# Peripheral_Circuit_A.net
KiCad netlist of a schematic drawn in Altium Designer
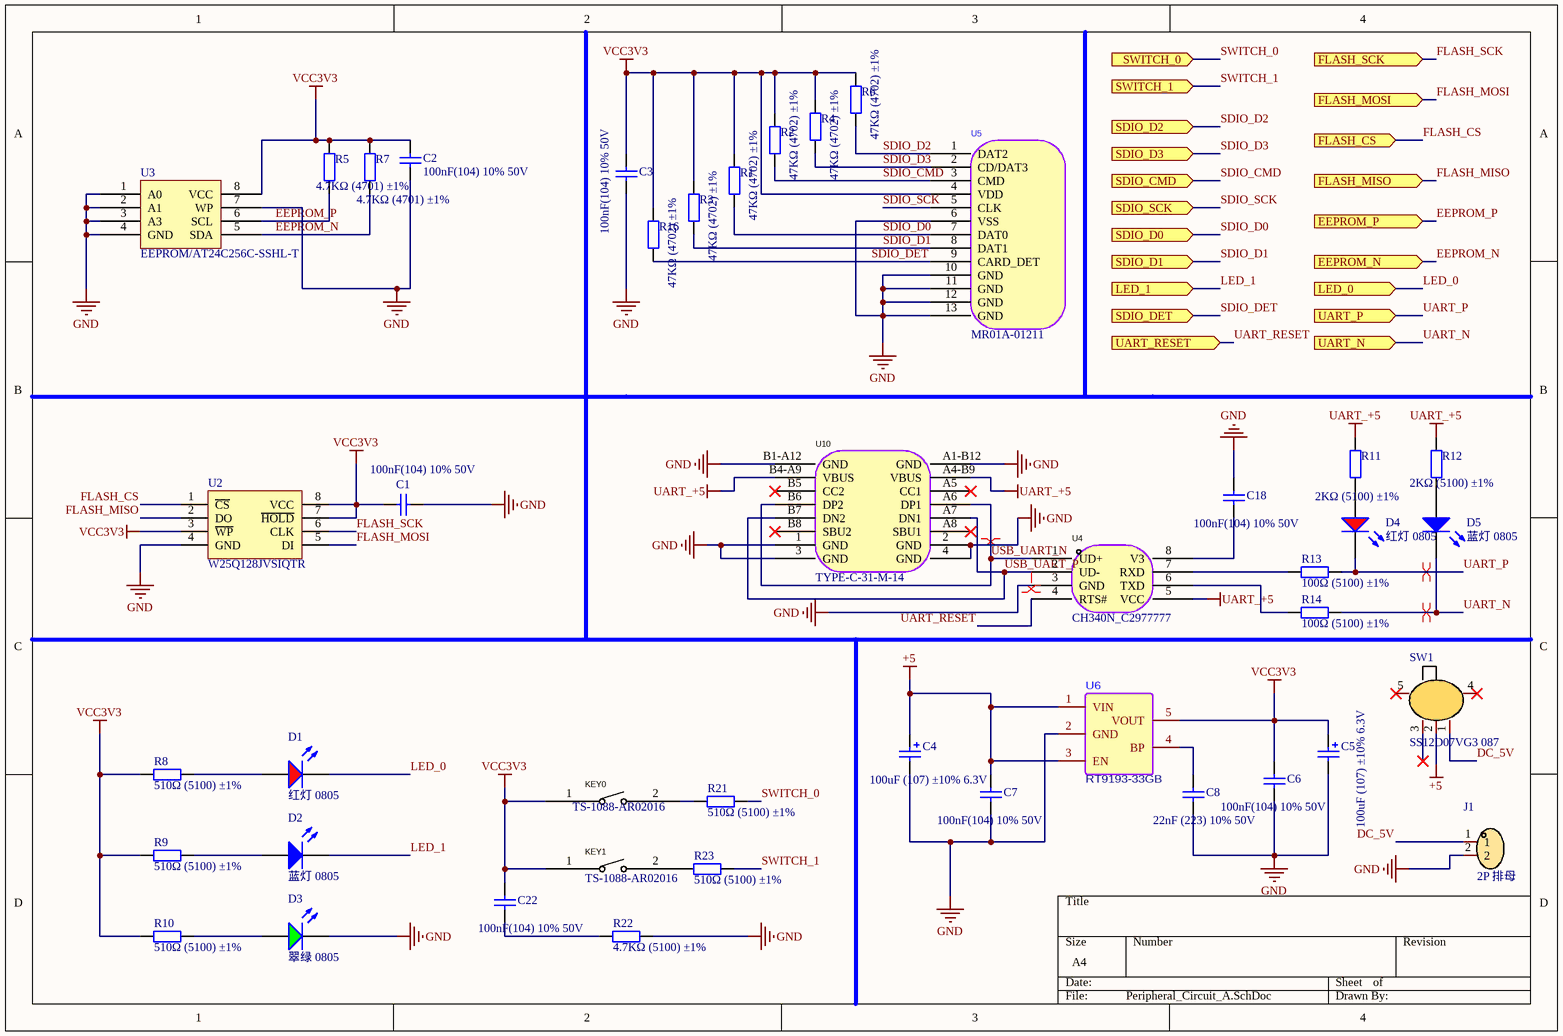
[diagram p0: Peripheral_Circuit_A.SchDoc]

(export (version "E")
  (design (tool "Eeschema 10.0.6"))
  (components
    (comp (ref "C1")
      (value "100nF(104) 10% 50V")
      (footprint "0805_C")
      (description "贴片电容")
      (libsource (lib "Miscellaneous Devices LC") (part "0805 100nF(104) 10% 50V"))
    )
    (comp (ref "C2")
      (value "100nF(104) 10% 50V")
      (footprint "0805_C")
      (description "贴片电容")
      (libsource (lib "Miscellaneous Devices LC") (part "0805 100nF(104) 10% 50V"))
    )
    (comp (ref "C3")
      (value "100nF(104) 10% 50V")
      (footprint "0805_C")
      (description "贴片电容")
      (libsource (lib "Miscellaneous Devices LC") (part "0805 100nF(104) 10% 50V"))
    )
    (comp (ref "C4")
      (value "100uF (107) ±10% 6.3V")
      (footprint "CASE-B_3528")
      (description "钽电容")
      (libsource (lib "Miscellaneous Devices LC") (part "3528 100uF (107) 10% 6.3V"))
    )
    (comp (ref "C5")
      (value "100uF (107) ±10% 6.3V")
      (footprint "CASE-B_3528")
      (description "钽电容")
      (libsource (lib "Miscellaneous Devices LC") (part "3528 100uF (107) 10% 6.3V"))
    )
    (comp (ref "C6")
      (value "100nF(104) 10% 50V")
      (footprint "0805_C")
      (description "贴片电容")
      (libsource (lib "Miscellaneous Devices LC") (part "0805 100nF(104) 10% 50V"))
    )
    (comp (ref "C7")
      (value "100nF(104) 10% 50V")
      (footprint "0805_C")
      (description "贴片电容")
      (libsource (lib "Miscellaneous Devices LC") (part "0805 100nF(104) 10% 50V"))
    )
    (comp (ref "C8")
      (value "22nF (223) 10% 50V")
      (footprint "0805_C")
      (description "贴片电容")
      (libsource (lib "Miscellaneous Devices LC") (part "0805 22nF (223) 10% 50V"))
    )
    (comp (ref "C18")
      (value "100nF(104) 10% 50V")
      (footprint "0805_C")
      (description "贴片电容")
      (libsource (lib "Miscellaneous Devices LC") (part "0805 100nF(104) 10% 50V"))
    )
    (comp (ref "C22")
      (value "100nF(104) 10% 50V")
      (footprint "0805_C")
      (description "贴片电容")
      (libsource (lib "Miscellaneous Devices LC") (part "0805 100nF(104) 10% 50V"))
    )
    (comp (ref "D1")
      (value "红灯 0805")
      (footprint "0805_LED_S1")
      (description "发光二极管")
      (libsource (lib "LED") (part "0805 红灯"))
    )
    (comp (ref "D2")
      (value "蓝灯 0805")
      (footprint "0805_LED_S1")
      (description "发光二极管")
      (libsource (lib "LED") (part "0805 蓝灯"))
    )
    (comp (ref "D3")
      (value "翠绿 0805")
      (footprint "0805_LED_S1")
      (description "发光二极管")
      (libsource (lib "LED") (part "0805 翠绿"))
    )
    (comp (ref "D4")
      (value "红灯 0805")
      (footprint "0805_LED_S1")
      (description "发光二极管")
      (libsource (lib "LED") (part "0805 红灯"))
    )
    (comp (ref "D5")
      (value "蓝灯 0805")
      (footprint "0805_LED_S1")
      (description "发光二极管")
      (libsource (lib "LED") (part "0805 蓝灯"))
    )
    (comp (ref "J1")
      (value "2P 排母")
      (footprint "PM254-1-02-W-8.5")
      (description "2p弯针")
      (fields
        (field (name "MANUFACTURER") "HCTL(华灿天禄)")
        (field (name "MANUFACTURER PART") "PM254-1-02-W-8.5")
      )
      (libsource (lib "EXTRA") (part "PM254-1-02-W-8.5"))
    )
    (comp (ref "KEY0")
      (value "TS-1088-AR02016")
      (footprint "SW-SMD_L3.9-W3.0-P4.45")
      (description "轻触开关")
      (fields (field (name "MANUFACTURER") "XUNPU(讯普)"))
      (libsource (lib "EXTRA") (part "TS-1088-AR02016"))
    )
    (comp (ref "KEY1")
      (value "TS-1088-AR02016")
      (footprint "SW-SMD_L3.9-W3.0-P4.45")
      (description "轻触开关")
      (fields (field (name "MANUFACTURER") "XUNPU(讯普)"))
      (libsource (lib "EXTRA") (part "TS-1088-AR02016"))
    )
    (comp (ref "R1")
      (value "47KΩ (4702) ±1%")
      (footprint "0805_R")
      (description "贴片电阻")
      (libsource (lib "Miscellaneous Devices LC") (part "0805 47KΩ (4702) 1%"))
    )
    (comp (ref "R2")
      (value "47KΩ (4702) ±1%")
      (footprint "0805_R")
      (description "贴片电阻")
      (libsource (lib "Miscellaneous Devices LC") (part "0805 47KΩ (4702) 1%"))
    )
    (comp (ref "R3")
      (value "47KΩ (4702) ±1%")
      (footprint "0805_R")
      (description "贴片电阻")
      (libsource (lib "Miscellaneous Devices LC") (part "0805 47KΩ (4702) 1%"))
    )
    (comp (ref "R4")
      (value "47KΩ (4702) ±1%")
      (footprint "0805_R")
      (description "贴片电阻")
      (libsource (lib "Miscellaneous Devices LC") (part "0805 47KΩ (4702) 1%"))
    )
    (comp (ref "R5")
      (value "4.7KΩ (4701) ±1%")
      (footprint "0805_R")
      (description "贴片电阻")
      (libsource (lib "Miscellaneous Devices LC") (part "0805 4.7KΩ (4701) 1%"))
    )
    (comp (ref "R6")
      (value "47KΩ (4702) ±1%")
      (footprint "0805_R")
      (description "贴片电阻")
      (libsource (lib "Miscellaneous Devices LC") (part "0805 47KΩ (4702) 1%"))
    )
    (comp (ref "R7")
      (value "4.7KΩ (4701) ±1%")
      (footprint "0805_R")
      (description "贴片电阻")
      (libsource (lib "Miscellaneous Devices LC") (part "0805 4.7KΩ (4701) 1%"))
    )
    (comp (ref "R8")
      (value "510Ω (5100) ±1%")
      (footprint "0805_R")
      (description "贴片电阻")
      (libsource (lib "Miscellaneous Devices LC") (part "0805 510Ω (5100) 1%"))
    )
    (comp (ref "R9")
      (value "510Ω (5100) ±1%")
      (footprint "0805_R")
      (description "贴片电阻")
      (libsource (lib "Miscellaneous Devices LC") (part "0805 510Ω (5100) 1%"))
    )
    (comp (ref "R10")
      (value "510Ω (5100) ±1%")
      (footprint "0805_R")
      (description "贴片电阻")
      (libsource (lib "Miscellaneous Devices LC") (part "0805 510Ω (5100) 1%"))
    )
    (comp (ref "R11")
      (value "2KΩ (5100) ±1%")
      (footprint "0805_R")
      (description "贴片电阻")
      (libsource (lib "") (part "0805 510Ω (5100) 1%_1"))
    )
    (comp (ref "R12")
      (value "2KΩ (5100) ±1%")
      (footprint "0805_R")
      (description "贴片电阻")
      (libsource (lib "") (part "0805 510Ω (5100) 1%_1"))
    )
    (comp (ref "R13")
      (value "100Ω (5100) ±1%")
      (footprint "0805_R")
      (description "贴片电阻")
      (libsource (lib "Miscellaneous Devices LC") (part "0805 510Ω (5100) 1%"))
    )
    (comp (ref "R14")
      (value "100Ω (5100) ±1%")
      (footprint "0805_R")
      (description "贴片电阻")
      (libsource (lib "Miscellaneous Devices LC") (part "0805 510Ω (5100) 1%"))
    )
    (comp (ref "R16")
      (value "47KΩ (4702) ±1%")
      (footprint "0805_R")
      (description "贴片电阻")
      (libsource (lib "Miscellaneous Devices LC") (part "0805 47KΩ (4702) 1%"))
    )
    (comp (ref "R21")
      (value "510Ω (5100) ±1%")
      (footprint "0805_R")
      (description "贴片电阻")
      (libsource (lib "Miscellaneous Devices LC") (part "0805 510Ω (5100) 1%"))
    )
    (comp (ref "R22")
      (value "4.7KΩ (5100) ±1%")
      (footprint "0805_R")
      (description "贴片电阻")
      (libsource (lib "") (part "0805 510Ω (5100) 1%_2"))
    )
    (comp (ref "R23")
      (value "510Ω (5100) ±1%")
      (footprint "0805_R")
      (description "贴片电阻")
      (libsource (lib "Miscellaneous Devices LC") (part "0805 510Ω (5100) 1%"))
    )
    (comp (ref "SW1")
      (value "SS12D07VG3 087")
      (footprint "SS12D07VG3")
      (description "直插贴片开关")
      (fields (field (name "MANUFACTURER") "SHOU HAN(首韩)"))
      (libsource (lib "EXTRA") (part "SS12D07VG3 087"))
    )
    (comp (ref "U2")
      (value "W25Q128JVSIQTR")
      (footprint "CH340_N")
      (description "Flash ROM")
      (libsource (lib "IC") (part "W25Q128JVSIQTR_[C97521]"))
    )
    (comp (ref "U3")
      (value "EEPROM/AT24C256C-SSHL-T")
      (footprint "CH340_N")
      (description "EEPROM")
      (libsource (lib "IC") (part "EEPROM/AT24C256C-SSHL-T_[C6482]"))
    )
    (comp (ref "U4")
      (value "CH340N_C2977777")
      (footprint "CH340_N")
      (description "TTL串口phy")
      (fields (field (name "DESIGNER") "U?"))
      (libsource (lib "EXTRA") (part "CH340N_C2977777"))
    )
    (comp (ref "U5")
      (value "MR01A-01211")
      (footprint "TF-SMD_MR01A-01211")
      (fields (field (name "MANUFACTURER") "ATOM(爱特姆)"))
      (libsource (lib "EXTRA") (part "MR01A-01211"))
    )
    (comp (ref "U6")
      (value "RT9193-33GB")
      (footprint "RT9193-33GB")
      (libsource (lib "EXTRA") (part "RT9193-33GB"))
    )
    (comp (ref "U10")
      (value "TYPE-C-31-M-14")
      (footprint "TYPE-C-31-M-14")
      (description "type-c接口")
      (fields (field (name "MANUFACTURER") "韩国韩荣"))
      (libsource (lib "EXTRA") (part "TYPE-C-31-M-14_1"))
    )
  )
  (nets
    (net (code "1") (name "+5") (class "Default")
      (node (ref "C4") (pin "1") (pinfunction "1_1") (pintype "passive"))
      (node (ref "C7") (pin "2") (pinfunction "2_2") (pintype "passive"))
      (node (ref "SW1") (pin "2") (pinfunction "2_2") (pintype "passive"))
      (node (ref "U6") (pin "1") (pinfunction "VIN_1") (pintype "passive"))
      (node (ref "U6") (pin "3") (pinfunction "EN_3") (pintype "passive"))
    )
    (net (code "2") (name "/DC_5V") (class "Default")
      (node (ref "J1") (pin "1") (pinfunction "1_1") (pintype "passive"))
      (node (ref "SW1") (pin "1") (pinfunction "1_1") (pintype "passive"))
    )
    (net (code "3") (name "/EEPROM_N") (class "Default")
      (node (ref "R7") (pin "1") (pinfunction "1_1") (pintype "passive"))
      (node (ref "U3") (pin "5") (pinfunction "SDA_5") (pintype "passive"))
    )
    (net (code "4") (name "/EEPROM_P") (class "Default")
      (node (ref "R5") (pin "1") (pinfunction "1_1") (pintype "passive"))
      (node (ref "U3") (pin "6") (pinfunction "SCL_6") (pintype "passive"))
    )
    (net (code "5") (name "/FLASH_CS") (class "Default")
      (node (ref "U2") (pin "1") (pinfunction "~{CS}_1") (pintype "passive"))
    )
    (net (code "6") (name "/FLASH_MISO") (class "Default")
      (node (ref "U2") (pin "2") (pinfunction "DO_2") (pintype "passive"))
    )
    (net (code "7") (name "/FLASH_MOSI") (class "Default")
      (node (ref "U2") (pin "5") (pinfunction "DI_5") (pintype "passive"))
    )
    (net (code "8") (name "/FLASH_SCK") (class "Default")
      (node (ref "U2") (pin "6") (pinfunction "CLK_6") (pintype "passive"))
    )
    (net (code "9") (name "/LED_0") (class "Default")
      (node (ref "D1") (pin "K") (pinfunction "K_K") (pintype "passive"))
    )
    (net (code "10") (name "/LED_1") (class "Default")
      (node (ref "D2") (pin "K") (pinfunction "K_K") (pintype "passive"))
    )
    (net (code "11") (name "/SDIO_CMD") (class "Default")
      (node (ref "R2") (pin "1") (pinfunction "1_1") (pintype "passive"))
      (node (ref "U5") (pin "3") (pinfunction "CMD_3") (pintype "passive"))
    )
    (net (code "12") (name "/SDIO_D0") (class "Default")
      (node (ref "R1") (pin "1") (pinfunction "1_1") (pintype "passive"))
      (node (ref "U5") (pin "7") (pinfunction "DAT0_7") (pintype "passive"))
    )
    (net (code "13") (name "/SDIO_D1") (class "Default")
      (node (ref "R3") (pin "1") (pinfunction "1_1") (pintype "passive"))
      (node (ref "U5") (pin "8") (pinfunction "DAT1_8") (pintype "passive"))
    )
    (net (code "14") (name "/SDIO_D2") (class "Default")
      (node (ref "R6") (pin "1") (pinfunction "1_1") (pintype "passive"))
      (node (ref "U5") (pin "1") (pinfunction "DAT2_1") (pintype "passive"))
    )
    (net (code "15") (name "/SDIO_D3") (class "Default")
      (node (ref "R4") (pin "1") (pinfunction "1_1") (pintype "passive"))
      (node (ref "U5") (pin "2") (pinfunction "CD/DAT3_2") (pintype "passive"))
    )
    (net (code "16") (name "/SDIO_DET") (class "Default")
      (node (ref "R16") (pin "1") (pinfunction "1_1") (pintype "passive"))
      (node (ref "U5") (pin "9") (pinfunction "CARD_DET_9") (pintype "passive"))
    )
    (net (code "17") (name "/SDIO_SCK") (class "Default")
      (node (ref "U5") (pin "5") (pinfunction "CLK_5") (pintype "passive"))
    )
    (net (code "18") (name "/SWITCH_0") (class "Default")
      (node (ref "R21") (pin "2") (pinfunction "2_2") (pintype "passive"))
    )
    (net (code "19") (name "/SWITCH_1") (class "Default")
      (node (ref "R23") (pin "2") (pinfunction "2_2") (pintype "passive"))
    )
    (net (code "20") (name "/UART_N") (class "Default")
      (node (ref "D5") (pin "K") (pinfunction "K_K") (pintype "passive"))
      (node (ref "R14") (pin "2") (pinfunction "2_2") (pintype "passive"))
    )
    (net (code "21") (name "/UART_P") (class "Default")
      (node (ref "D4") (pin "K") (pinfunction "K_K") (pintype "passive"))
      (node (ref "R13") (pin "2") (pinfunction "2_2") (pintype "passive"))
    )
    (net (code "22") (name "/UART_RESET") (class "Default")
      (node (ref "U4") (pin "4") (pinfunction "RTS#_4") (pintype "passive"))
    )
    (net (code "23") (name "/USB_UART_N") (class "Default")
      (node (ref "U10") (pin "A6") (pinfunction "DP1_A6") (pintype "passive"))
      (node (ref "U10") (pin "B6") (pinfunction "DP2_B6") (pintype "passive"))
      (node (ref "U4") (pin "1") (pinfunction "UD+_1") (pintype "passive"))
    )
    (net (code "24") (name "/USB_UART_P") (class "Default")
      (node (ref "U10") (pin "A7") (pinfunction "DN1_A7") (pintype "passive"))
      (node (ref "U10") (pin "B7") (pinfunction "DN2_B7") (pintype "passive"))
      (node (ref "U4") (pin "2") (pinfunction "UD-_2") (pintype "passive"))
    )
    (net (code "25") (name "GND") (class "Default")
      (node (ref "C1") (pin "2") (pinfunction "2_2") (pintype "passive"))
      (node (ref "C18") (pin "1") (pinfunction "1_1") (pintype "passive"))
      (node (ref "C2") (pin "1") (pinfunction "1_1") (pintype "passive"))
      (node (ref "C3") (pin "1") (pinfunction "1_1") (pintype "passive"))
      (node (ref "C4") (pin "2") (pinfunction "2_2") (pintype "passive"))
      (node (ref "C5") (pin "2") (pinfunction "2_2") (pintype "passive"))
      (node (ref "C6") (pin "1") (pinfunction "1_1") (pintype "passive"))
      (node (ref "C7") (pin "1") (pinfunction "1_1") (pintype "passive"))
      (node (ref "C8") (pin "1") (pinfunction "1_1") (pintype "passive"))
      (node (ref "D3") (pin "K") (pinfunction "K_K") (pintype "passive"))
      (node (ref "J1") (pin "2") (pinfunction "2_2") (pintype "passive"))
      (node (ref "R22") (pin "1") (pinfunction "1_1") (pintype "passive"))
      (node (ref "U10") (pin "1") (pinfunction "GND_1") (pintype "passive"))
      (node (ref "U10") (pin "2") (pinfunction "GND_2") (pintype "passive"))
      (node (ref "U10") (pin "3") (pinfunction "GND_3") (pintype "passive"))
      (node (ref "U10") (pin "4") (pinfunction "GND_4") (pintype "passive"))
      (node (ref "U10") (pin "A1-B12") (pinfunction "GND_A1-B12") (pintype "passive"))
      (node (ref "U10") (pin "B1-A12") (pinfunction "GND_B1-A12") (pintype "passive"))
      (node (ref "U2") (pin "4") (pinfunction "GND_4") (pintype "passive"))
      (node (ref "U3") (pin "1") (pinfunction "A0_1") (pintype "passive"))
      (node (ref "U3") (pin "2") (pinfunction "A1_2") (pintype "passive"))
      (node (ref "U3") (pin "3") (pinfunction "A3_3") (pintype "passive"))
      (node (ref "U3") (pin "4") (pinfunction "GND_4") (pintype "passive"))
      (node (ref "U3") (pin "7") (pinfunction "WP_7") (pintype "passive"))
      (node (ref "U4") (pin "3") (pinfunction "GND_3") (pintype "passive"))
      (node (ref "U5") (pin "10") (pinfunction "GND_10") (pintype "passive"))
      (node (ref "U5") (pin "11") (pinfunction "GND_11") (pintype "passive"))
      (node (ref "U5") (pin "12") (pinfunction "GND_12") (pintype "passive"))
      (node (ref "U5") (pin "13") (pinfunction "GND_13") (pintype "passive"))
      (node (ref "U5") (pin "6") (pinfunction "VSS_6") (pintype "passive"))
      (node (ref "U6") (pin "2") (pinfunction "GND_2") (pintype "passive"))
    )
    (net (code "26") (name "Net-(C22-Pad1)") (class "Default")
      (node (ref "C22") (pin "1") (pinfunction "1_1") (pintype "passive"))
      (node (ref "R22") (pin "2") (pinfunction "2_2") (pintype "passive"))
    )
    (net (code "27") (name "Net-(D1-PadA)") (class "Default")
      (node (ref "D1") (pin "A") (pinfunction "A_A") (pintype "passive"))
      (node (ref "R8") (pin "2") (pinfunction "2_2") (pintype "passive"))
    )
    (net (code "28") (name "Net-(D2-PadA)") (class "Default")
      (node (ref "D2") (pin "A") (pinfunction "A_A") (pintype "passive"))
      (node (ref "R9") (pin "2") (pinfunction "2_2") (pintype "passive"))
    )
    (net (code "29") (name "Net-(D3-PadA)") (class "Default")
      (node (ref "D3") (pin "A") (pinfunction "A_A") (pintype "passive"))
      (node (ref "R10") (pin "2") (pinfunction "2_2") (pintype "passive"))
    )
    (net (code "30") (name "Net-(D4-PadA)") (class "Default")
      (node (ref "D4") (pin "A") (pinfunction "A_A") (pintype "passive"))
      (node (ref "R11") (pin "1") (pinfunction "1_1") (pintype "passive"))
    )
    (net (code "31") (name "Net-(D5-PadA)") (class "Default")
      (node (ref "D5") (pin "A") (pinfunction "A_A") (pintype "passive"))
      (node (ref "R12") (pin "1") (pinfunction "1_1") (pintype "passive"))
    )
    (net (code "32") (name "Net-(KEY0-Pad2)") (class "Default")
      (node (ref "KEY0") (pin "2") (pinfunction "2_2") (pintype "passive"))
      (node (ref "R21") (pin "1") (pinfunction "1_1") (pintype "passive"))
    )
    (net (code "33") (name "Net-(KEY1-Pad2)") (class "Default")
      (node (ref "KEY1") (pin "2") (pinfunction "2_2") (pintype "passive"))
      (node (ref "R23") (pin "1") (pinfunction "1_1") (pintype "passive"))
    )
    (net (code "34") (name "Net-(U4-RXD)") (class "Default")
      (node (ref "R13") (pin "1") (pinfunction "1_1") (pintype "passive"))
      (node (ref "U4") (pin "7") (pinfunction "RXD_7") (pintype "passive"))
    )
    (net (code "35") (name "Net-(U4-TXD)") (class "Default")
      (node (ref "R14") (pin "1") (pinfunction "1_1") (pintype "passive"))
      (node (ref "U4") (pin "6") (pinfunction "TXD_6") (pintype "passive"))
    )
    (net (code "36") (name "Net-(U4-V3)") (class "Default")
      (node (ref "C18") (pin "2") (pinfunction "2_2") (pintype "passive"))
      (node (ref "U4") (pin "8") (pinfunction "V3_8") (pintype "passive"))
    )
    (net (code "37") (name "Net-(U6-BP)") (class "Default")
      (node (ref "C8") (pin "2") (pinfunction "2_2") (pintype "passive"))
      (node (ref "U6") (pin "4") (pinfunction "BP_4") (pintype "passive"))
    )
    (net (code "38") (name "UART_+5") (class "Default")
      (node (ref "R11") (pin "2") (pinfunction "2_2") (pintype "passive"))
      (node (ref "R12") (pin "2") (pinfunction "2_2") (pintype "passive"))
      (node (ref "U10") (pin "A4-B9") (pinfunction "VBUS_A4-B9") (pintype "passive"))
      (node (ref "U10") (pin "B4-A9") (pinfunction "VBUS_B4-A9") (pintype "passive"))
      (node (ref "U4") (pin "5") (pinfunction "VCC_5") (pintype "passive"))
    )
    (net (code "39") (name "VCC3V3") (class "Default")
      (node (ref "C1") (pin "1") (pinfunction "1_1") (pintype "passive"))
      (node (ref "C2") (pin "2") (pinfunction "2_2") (pintype "passive"))
      (node (ref "C22") (pin "2") (pinfunction "2_2") (pintype "passive"))
      (node (ref "C3") (pin "2") (pinfunction "2_2") (pintype "passive"))
      (node (ref "C5") (pin "1") (pinfunction "1_1") (pintype "passive"))
      (node (ref "C6") (pin "2") (pinfunction "2_2") (pintype "passive"))
      (node (ref "KEY0") (pin "1") (pinfunction "1_1") (pintype "passive"))
      (node (ref "KEY1") (pin "1") (pinfunction "1_1") (pintype "passive"))
      (node (ref "R1") (pin "2") (pinfunction "2_2") (pintype "passive"))
      (node (ref "R10") (pin "1") (pinfunction "1_1") (pintype "passive"))
      (node (ref "R16") (pin "2") (pinfunction "2_2") (pintype "passive"))
      (node (ref "R2") (pin "2") (pinfunction "2_2") (pintype "passive"))
      (node (ref "R3") (pin "2") (pinfunction "2_2") (pintype "passive"))
      (node (ref "R4") (pin "2") (pinfunction "2_2") (pintype "passive"))
      (node (ref "R5") (pin "2") (pinfunction "2_2") (pintype "passive"))
      (node (ref "R6") (pin "2") (pinfunction "2_2") (pintype "passive"))
      (node (ref "R7") (pin "2") (pinfunction "2_2") (pintype "passive"))
      (node (ref "R8") (pin "1") (pinfunction "1_1") (pintype "passive"))
      (node (ref "R9") (pin "1") (pinfunction "1_1") (pintype "passive"))
      (node (ref "U2") (pin "3") (pinfunction "~{WP}_3") (pintype "passive"))
      (node (ref "U2") (pin "7") (pinfunction "~{HOLD}_7") (pintype "passive"))
      (node (ref "U2") (pin "8") (pinfunction "VCC_8") (pintype "passive"))
      (node (ref "U3") (pin "8") (pinfunction "VCC_8") (pintype "passive"))
      (node (ref "U5") (pin "4") (pinfunction "VDD_4") (pintype "passive"))
      (node (ref "U6") (pin "5") (pinfunction "VOUT_5") (pintype "passive"))
    )
    (net (code "40") (name "unconnected-(SW1-Pad3)") (class "Default")
      (node (ref "SW1") (pin "3") (pinfunction "3_3") (pintype "passive+no_connect"))
    )
    (net (code "41") (name "unconnected-(SW1-Pad4)") (class "Default")
      (node (ref "SW1") (pin "4") (pinfunction "4_4") (pintype "passive+no_connect"))
    )
    (net (code "42") (name "unconnected-(SW1-Pad5)") (class "Default")
      (node (ref "SW1") (pin "5") (pinfunction "5_5") (pintype "passive+no_connect"))
    )
    (net (code "43") (name "unconnected-(U10-CC1-PadA5)") (class "Default")
      (node (ref "U10") (pin "A5") (pinfunction "CC1_A5") (pintype "passive+no_connect"))
    )
    (net (code "44") (name "unconnected-(U10-CC2-PadB5)") (class "Default")
      (node (ref "U10") (pin "B5") (pinfunction "CC2_B5") (pintype "passive+no_connect"))
    )
    (net (code "45") (name "unconnected-(U10-SBU1-PadA8)") (class "Default")
      (node (ref "U10") (pin "A8") (pinfunction "SBU1_A8") (pintype "passive+no_connect"))
    )
    (net (code "46") (name "unconnected-(U10-SBU2-PadB8)") (class "Default")
      (node (ref "U10") (pin "B8") (pinfunction "SBU2_B8") (pintype "passive+no_connect"))
    )
  )
)
